# power.net
KiCad netlist of a schematic drawn in Altium Designer
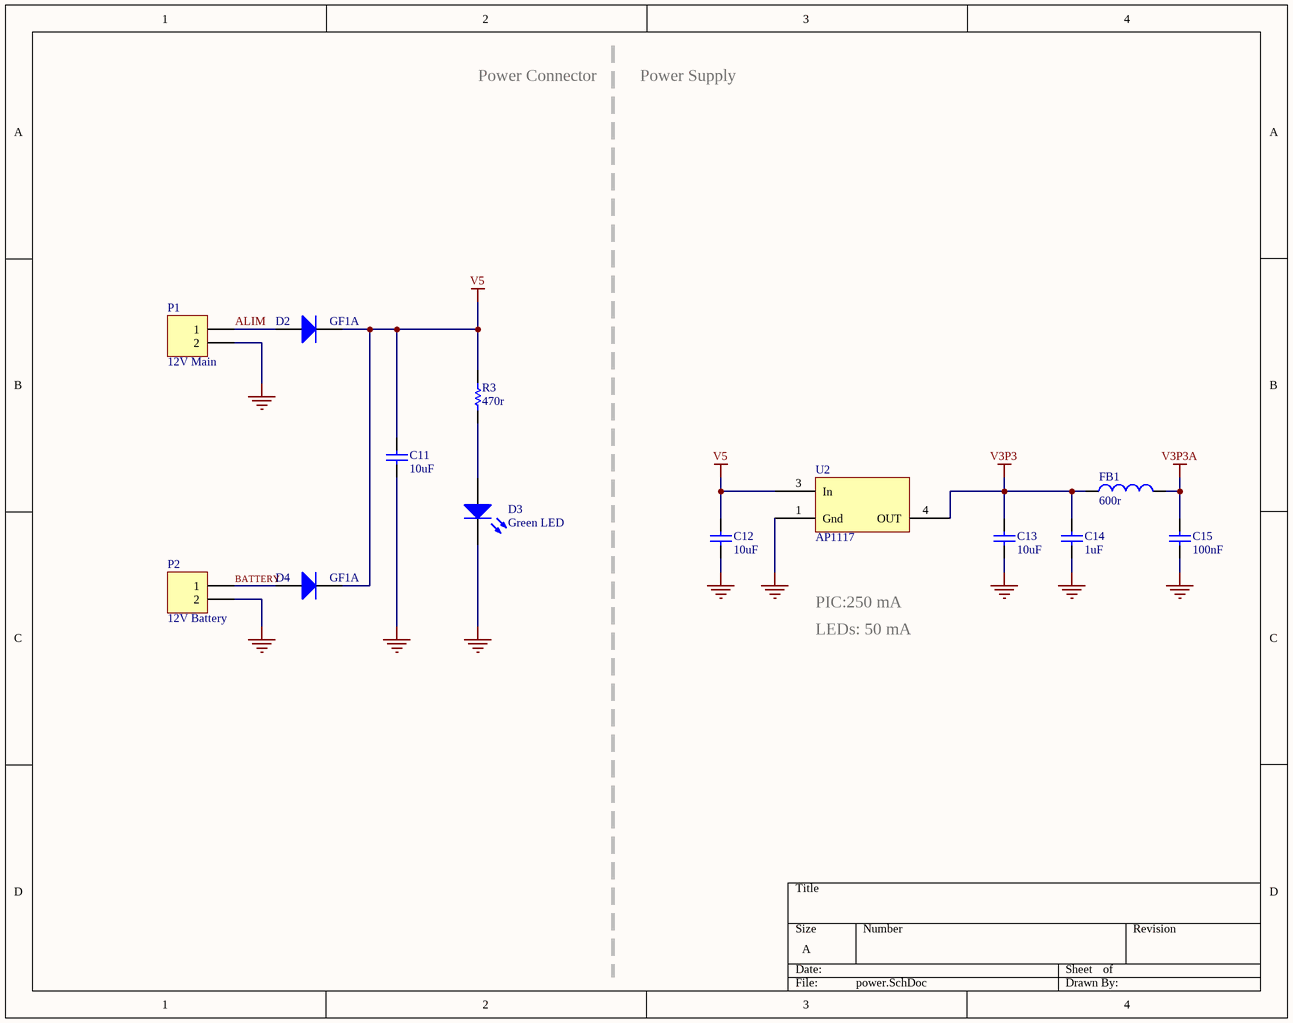
[diagram p0: power.SchDoc]

(export (version "E")
  (design (tool "Eeschema 10.0.6"))
  (components
    (comp (ref "C11")
      (value "10uF")
      (footprint "CAPC2012N")
      (description "Capacitor")
      (fields (field (name "PUBLISHER") "Altium Limited"))
      (libsource (lib "Miscellaneous Devices") (part "Cap"))
    )
    (comp (ref "C12")
      (value "10uF")
      (footprint "CAPC2012N")
      (description "Capacitor")
      (fields (field (name "PUBLISHER") "Altium Limited"))
      (libsource (lib "Miscellaneous Devices") (part "Cap"))
    )
    (comp (ref "C13")
      (value "10uF")
      (footprint "CAPC2012N")
      (description "Capacitor")
      (fields (field (name "PUBLISHER") "Altium Limited"))
      (libsource (lib "Miscellaneous Devices") (part "Cap"))
    )
    (comp (ref "C14")
      (value "1uF")
      (footprint "CAPC1608N")
      (description "Capacitor")
      (fields (field (name "PUBLISHER") "Altium Limited"))
      (libsource (lib "Miscellaneous Devices") (part "Cap"))
    )
    (comp (ref "C15")
      (value "100nF")
      (footprint "CAPC1608N")
      (description "Capacitor")
      (fields (field (name "PUBLISHER") "Altium Limited"))
      (libsource (lib "Miscellaneous Devices") (part "Cap"))
    )
    (comp (ref "D2")
      (value "GF1A")
      (footprint "SMA/DO-214AC_21")
      (description "Default Diode")
      (fields (field (name "PUBLISHER") "Altium Limited"))
      (libsource (lib "Miscellaneous Devices") (part "Diode"))
    )
    (comp (ref "D3")
      (value "Green LED")
      (footprint "LED 0805")
      (description "Typical INFRARED GaAs LED")
      (fields (field (name "PUBLISHER") "Altium Limited"))
      (libsource (lib "Miscellaneous Devices") (part "LED0"))
    )
    (comp (ref "D4")
      (value "GF1A")
      (footprint "SMA/DO-214AC_21")
      (description "Default Diode")
      (fields (field (name "PUBLISHER") "Altium Limited"))
      (libsource (lib "Miscellaneous Devices") (part "Diode"))
    )
    (comp (ref "FB1")
      (value "600r")
      (footprint "INDC1608AN")
      (description "Inductor")
      (fields (field (name "PUBLISHER") "Altium Limited"))
      (libsource (lib "Miscellaneous Devices") (part "Inductor"))
    )
    (comp (ref "P1")
      (value "12V Main")
      (footprint "PHOENIX_1985195")
      (description "Header, 2-Pin")
      (fields (field (name "PUBLISHER") "Altium Limited"))
      (libsource (lib "Miscellaneous Connectors") (part "Header 2"))
    )
    (comp (ref "P2")
      (value "12V Battery")
      (footprint "PHOENIX_1985195")
      (description "Header, 2-Pin")
      (fields (field (name "PUBLISHER") "Altium Limited"))
      (libsource (lib "Miscellaneous Connectors") (part "Header 2"))
    )
    (comp (ref "R3")
      (value "470r")
      (footprint "RESC1608N")
      (description "Resistor")
      (fields (field (name "PUBLISHER") "Altium Limited"))
      (libsource (lib "Miscellaneous Devices") (part "Res1"))
    )
    (comp (ref "U2")
      (value "AP1117")
      (footprint "TD03B_N")
      (description "1A LDO, 18V input, DPAK")
      (libsource (lib "Schlib1") (part "AP1117"))
    )
  )
  (nets
    (net (code "1") (name "/ALIM") (class "Default")
      (node (ref "D2") (pin "1") (pinfunction "A_1") (pintype "passive"))
      (node (ref "P1") (pin "1") (pinfunction "1_1") (pintype "passive"))
    )
    (net (code "2") (name "/BATTERY") (class "Default")
      (node (ref "D4") (pin "1") (pinfunction "A_1") (pintype "passive"))
      (node (ref "P2") (pin "1") (pinfunction "1_1") (pintype "passive"))
    )
    (net (code "3") (name "GND") (class "Default")
      (node (ref "C11") (pin "2") (pinfunction "2_2") (pintype "passive"))
      (node (ref "C12") (pin "1") (pinfunction "1_1") (pintype "passive"))
      (node (ref "C13") (pin "1") (pinfunction "1_1") (pintype "passive"))
      (node (ref "C14") (pin "1") (pinfunction "1_1") (pintype "passive"))
      (node (ref "C15") (pin "1") (pinfunction "1_1") (pintype "passive"))
      (node (ref "D3") (pin "2") (pinfunction "K_2") (pintype "passive"))
      (node (ref "P1") (pin "2") (pinfunction "2_2") (pintype "passive"))
      (node (ref "P2") (pin "2") (pinfunction "2_2") (pintype "passive"))
      (node (ref "U2") (pin "1") (pinfunction "Gnd_1") (pintype "power_in"))
    )
    (net (code "4") (name "Net-(D3-A)") (class "Default")
      (node (ref "D3") (pin "1") (pinfunction "A_1") (pintype "passive"))
      (node (ref "R3") (pin "1") (pinfunction "1_1") (pintype "passive"))
    )
    (net (code "5") (name "V3P3") (class "Default")
      (node (ref "C13") (pin "2") (pinfunction "2_2") (pintype "passive"))
      (node (ref "C14") (pin "2") (pinfunction "2_2") (pintype "passive"))
      (node (ref "FB1") (pin "1") (pinfunction "1_1") (pintype "passive"))
      (node (ref "U2") (pin "4") (pinfunction "OUT_4") (pintype "power_in"))
    )
    (net (code "6") (name "V3P3A") (class "Default")
      (node (ref "C15") (pin "2") (pinfunction "2_2") (pintype "passive"))
      (node (ref "FB1") (pin "2") (pinfunction "2_2") (pintype "passive"))
    )
    (net (code "7") (name "V5") (class "Default")
      (node (ref "C11") (pin "1") (pinfunction "1_1") (pintype "passive"))
      (node (ref "C12") (pin "2") (pinfunction "2_2") (pintype "passive"))
      (node (ref "D2") (pin "2") (pinfunction "K_2") (pintype "passive"))
      (node (ref "D4") (pin "2") (pinfunction "K_2") (pintype "passive"))
      (node (ref "R3") (pin "2") (pinfunction "2_2") (pintype "passive"))
      (node (ref "U2") (pin "3") (pinfunction "In_3") (pintype "power_in"))
    )
  )
)
